# Regulators.net
KiCad netlist of a schematic drawn in Altium Designer
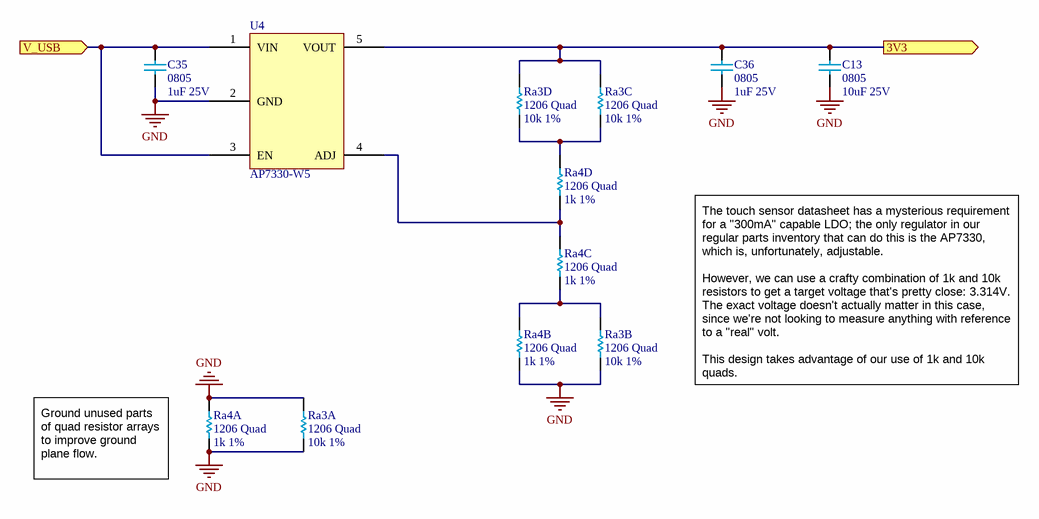
[diagram p0: Regulators.SchDoc]

(export (version "E")
  (design (tool "Eeschema 10.0.6"))
  (components
    (comp (ref "C13")
      (value "0805")
      (footprint "0805")
      (description "0805, X5R or better")
      (fields (field (name "ALTIUM_VALUE") "10uF 25V"))
      (libsource (lib "Chip_Passives") (part "Cap 10uF 25V"))
    )
    (comp (ref "C35")
      (value "0805")
      (footprint "0805")
      (description "0805, X5R or better")
      (fields (field (name "ALTIUM_VALUE") "1uF 25V"))
      (libsource (lib "Chip_Passives") (part "Cap 1uF 25V"))
    )
    (comp (ref "C36")
      (value "0805")
      (footprint "0805")
      (description "0805, X5R or better")
      (fields (field (name "ALTIUM_VALUE") "1uF 25V"))
      (libsource (lib "Chip_Passives") (part "Cap 1uF 25V"))
    )
    (comp (ref "Ra3")
      (value "1206 Quad")
      (footprint "4x 10k 1% - CAC-80P320X160-8M")
      (description "Chip resistor")
      (fields (field (name "ALTIUM_VALUE") "10k 1%"))
      (libsource (lib "Chip_Passives") (part "Quad Res 10k 1% 1206"))
    )
    (comp (ref "Ra4")
      (value "1206 Quad")
      (footprint "4x 1k 1% - CAC-80P320X160-8M")
      (description "Chip resistor")
      (fields (field (name "ALTIUM_VALUE") "1k 1%"))
      (libsource (lib "Chip_Passives") (part "Quad Res 1k 1% 1206"))
    )
    (comp (ref "U4")
      (value "AP7330-W5")
      (footprint "AP7330-W5 - SOT95P270X145-5N")
      (description "300mA HIGH PSRR LOW NOISE LDO WITH ENABLE")
      (libsource (lib "PowerSupply") (part "AP7330-W5"))
    )
  )
  (nets
    (net (code "1") (name "/3V3") (class "Default")
      (node (ref "C13") (pin "2") (pinfunction "2_2") (pintype "passive"))
      (node (ref "C36") (pin "2") (pinfunction "2_2") (pintype "passive"))
      (node (ref "Ra3") (pin "3") (pinfunction "3_3") (pintype "passive"))
      (node (ref "Ra3") (pin "4") (pinfunction "4_4") (pintype "passive"))
      (node (ref "U4") (pin "5") (pinfunction "VOUT_5") (pintype "passive"))
    )
    (net (code "2") (name "/V_USB") (class "Default")
      (node (ref "C35") (pin "2") (pinfunction "2_2") (pintype "passive"))
      (node (ref "U4") (pin "1") (pinfunction "VIN_1") (pintype "passive"))
      (node (ref "U4") (pin "3") (pinfunction "EN_3") (pintype "passive"))
    )
    (net (code "3") (name "GND") (class "Default")
      (node (ref "C13") (pin "1") (pinfunction "1_1") (pintype "passive"))
      (node (ref "C35") (pin "1") (pinfunction "1_1") (pintype "passive"))
      (node (ref "C36") (pin "1") (pinfunction "1_1") (pintype "passive"))
      (node (ref "Ra3") (pin "1") (pinfunction "1_1") (pintype "passive"))
      (node (ref "Ra3") (pin "2") (pinfunction "2_2") (pintype "passive"))
      (node (ref "Ra3") (pin "8") (pinfunction "8_8") (pintype "passive"))
      (node (ref "Ra4") (pin "1") (pinfunction "1_1") (pintype "passive"))
      (node (ref "Ra4") (pin "7") (pinfunction "7_7") (pintype "passive"))
      (node (ref "Ra4") (pin "8") (pinfunction "8_8") (pintype "passive"))
      (node (ref "U4") (pin "2") (pinfunction "GND_2") (pintype "passive"))
    )
    (net (code "4") (name "Net-(Ra3-Pad5)") (class "Default")
      (node (ref "Ra3") (pin "5") (pinfunction "5_5") (pintype "passive"))
      (node (ref "Ra3") (pin "6") (pinfunction "6_6") (pintype "passive"))
      (node (ref "Ra4") (pin "4") (pinfunction "4_4") (pintype "passive"))
    )
    (net (code "5") (name "Net-(Ra3-Pad7)") (class "Default")
      (node (ref "Ra3") (pin "7") (pinfunction "7_7") (pintype "passive"))
      (node (ref "Ra4") (pin "2") (pinfunction "2_2") (pintype "passive"))
      (node (ref "Ra4") (pin "3") (pinfunction "3_3") (pintype "passive"))
    )
    (net (code "6") (name "Net-(U4-ADJ)") (class "Default")
      (node (ref "Ra4") (pin "5") (pinfunction "5_5") (pintype "passive"))
      (node (ref "Ra4") (pin "6") (pinfunction "6_6") (pintype "passive"))
      (node (ref "U4") (pin "4") (pinfunction "ADJ_4") (pintype "passive"))
    )
  )
)
